# ControlStage.net
KiCad netlist of a schematic drawn in Altium Designer
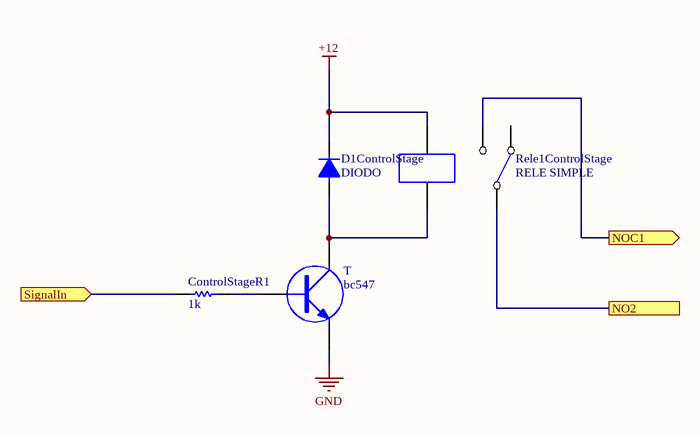
[diagram p0: ControlStage.SchDoc]

(export (version "E")
  (design (tool "Eeschema 10.0.6"))
  (components
    (comp (ref "ControlStageR1") (value "1k") (footprint "RES400") (libsource (lib "LIBEBAL") (part "RES")))
    (comp (ref "D1ControlStage")
      (value "DIODO")
      (footprint "DO41")
      (libsource (lib "LIBEBAL") (part "DIODO"))
    )
    (comp (ref "Rele1ControlStage")
      (value "RELE SIMPLE")
      (footprint "RELE SERIE 964")
      (libsource (lib "LIBEBAL") (part "RELE SIMPLE"))
    )
    (comp (ref "T")
      (value "bc547")
      (footprint "TO-220 H - DISIPADOR")
      (libsource (lib "LIBEBAL") (part "TRANSISTOR NPN"))
    )
  )
  (nets
    (net (code "1") (name "+12") (class "Default")
      (node (ref "D1ControlStage") (pin "2") (pinfunction "2_2") (pintype "passive"))
      (node (ref "Rele1ControlStage") (pin "B1") (pinfunction "B1_B1") (pintype "passive"))
    )
    (net (code "2") (name "/NO2") (class "Default")
      (node (ref "Rele1ControlStage") (pin "C1") (pinfunction "C1_C1") (pintype "passive"))
    )
    (net (code "3") (name "/NOC1") (class "Default")
      (node (ref "Rele1ControlStage") (pin "NA1") (pinfunction "NA1_NA1") (pintype "passive"))
    )
    (net (code "4") (name "/SignalIn") (class "Default")
      (node (ref "ControlStageR1") (pin "1") (pinfunction "1_1") (pintype "passive"))
    )
    (net (code "5") (name "GND") (class "Default")
      (node (ref "T") (pin "3") (pinfunction "E_3") (pintype "passive"))
    )
    (net (code "6") (name "Net-(T-B)") (class "Default")
      (node (ref "ControlStageR1") (pin "2") (pinfunction "2_2") (pintype "passive"))
      (node (ref "T") (pin "1") (pinfunction "B_1") (pintype "passive"))
    )
    (net (code "7") (name "Net-(T-C)") (class "Default")
      (node (ref "D1ControlStage") (pin "1") (pinfunction "1_1") (pintype "passive"))
      (node (ref "Rele1ControlStage") (pin "B2") (pinfunction "B2_B2") (pintype "passive"))
      (node (ref "T") (pin "2") (pinfunction "C_2") (pintype "passive"))
    )
    (net (code "8") (name "unconnected-(Rele1ControlStage-PadNC1)") (class "Default")
      (node (ref "Rele1ControlStage") (pin "NC1") (pinfunction "NC1_NC1") (pintype "passive"))
    )
  )
)
